# platform.net
KiCad netlist of a schematic drawn in EAGLE
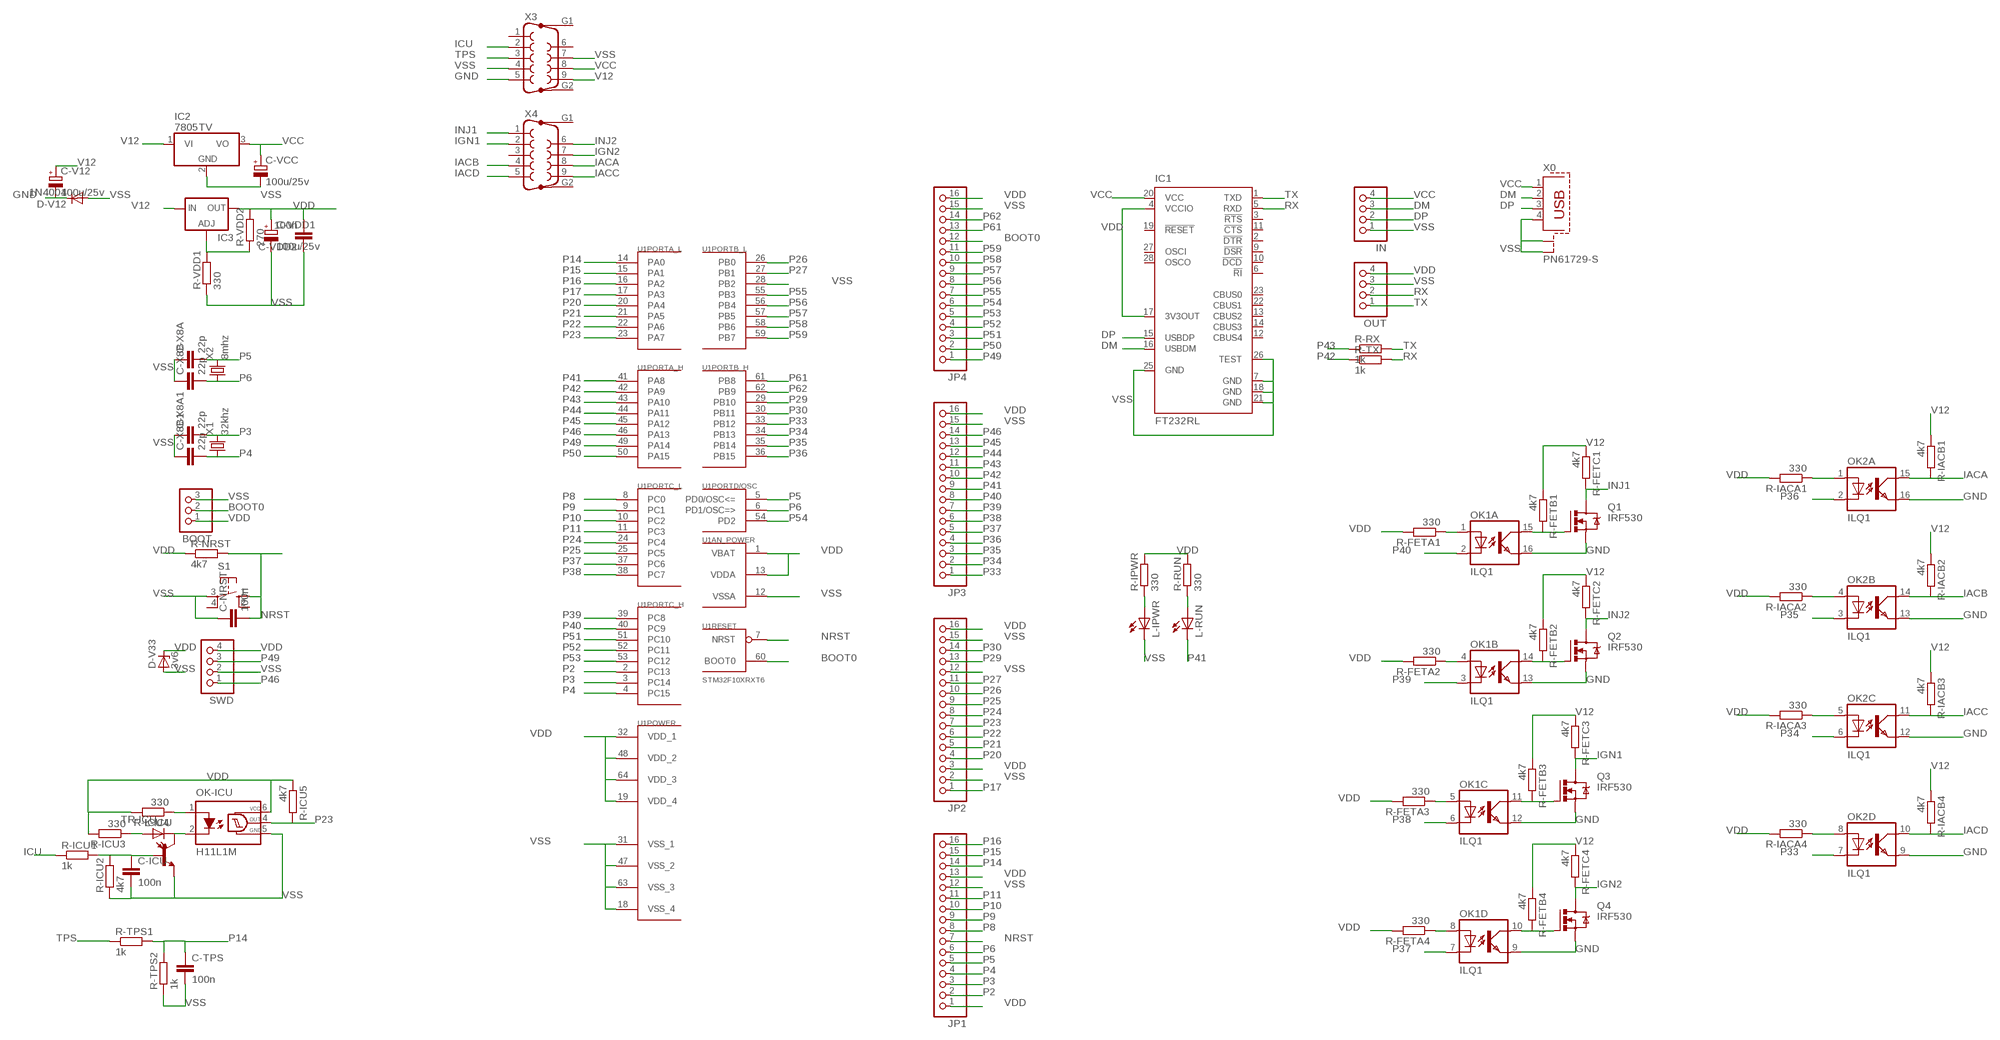
[diagram p0: schematic, sheet 1]

(export (version "E")
  (design (tool "Eeschema 10.0.6"))
  (components
    (comp (ref "BOOT")
      (value "PINHD-1X3")
      (footprint "eagle-import:1X03")
      (libsource (lib "eagle-import") (part "PINHD-1X3"))
    )
    (comp (ref "C-ICU")
      (value "100n")
      (footprint "eagle-import:C050-024X044")
      (libsource (lib "eagle-import") (part "C-EU050-024X044"))
    )
    (comp (ref "C-NRST")
      (value "100n")
      (footprint "eagle-import:C050-024X044")
      (libsource (lib "eagle-import") (part "C-EU050-024X044"))
    )
    (comp (ref "C-TPS")
      (value "100n")
      (footprint "eagle-import:C050-024X044")
      (libsource (lib "eagle-import") (part "C-EU050-024X044"))
    )
    (comp (ref "C-V12")
      (value "100u/25v")
      (footprint "eagle-import:E2-5")
      (libsource (lib "eagle-import") (part "CPOL-EUE2-5"))
    )
    (comp (ref "C-VCC")
      (value "100u/25v")
      (footprint "eagle-import:E2-5")
      (libsource (lib "eagle-import") (part "CPOL-EUE2-5"))
    )
    (comp (ref "C-VDD1")
      (value "100u/25v")
      (footprint "eagle-import:E2-5")
      (libsource (lib "eagle-import") (part "CPOL-EUE2-5"))
    )
    (comp (ref "C-VDD2")
      (value "100n")
      (footprint "eagle-import:C050-024X044")
      (libsource (lib "eagle-import") (part "C-EU050-024X044"))
    )
    (comp (ref "C-X8A")
      (value "22p")
      (footprint "eagle-import:C025-024X044")
      (libsource (lib "eagle-import") (part "C-EU025-024X044"))
    )
    (comp (ref "C-X8A1")
      (value "22p")
      (footprint "eagle-import:C025-024X044")
      (libsource (lib "eagle-import") (part "C-EU025-024X044"))
    )
    (comp (ref "C-X8B")
      (value "22p")
      (footprint "eagle-import:C025-024X044")
      (libsource (lib "eagle-import") (part "C-EU025-024X044"))
    )
    (comp (ref "C-X8B1")
      (value "22p")
      (footprint "eagle-import:C025-024X044")
      (libsource (lib "eagle-import") (part "C-EU025-024X044"))
    )
    (comp (ref "D-V12")
      (value "1N4004")
      (footprint "eagle-import:DO41-10")
      (libsource (lib "eagle-import") (part "1N4004"))
    )
    (comp (ref "D-V33")
      (value "3v6")
      (footprint "eagle-import:ZDIO-7.5")
      (libsource (lib "eagle-import") (part "ZENER-DIODEZD-7.5"))
    )
    (comp (ref "IC1")
      (value "FT232RL")
      (footprint "eagle-import:SSOP28")
      (libsource (lib "eagle-import") (part "FT232RL"))
    )
    (comp (ref "IC2")
      (value "7805TV")
      (footprint "eagle-import:TO220V")
      (libsource (lib "eagle-import") (part "78TV05"))
    )
    (comp (ref "IC3")
      (value "LM317TS")
      (footprint "eagle-import:317TS")
      (libsource (lib "eagle-import") (part "LM317TS"))
    )
    (comp (ref "IN")
      (value "PINHD-1X4")
      (footprint "eagle-import:1X04")
      (libsource (lib "eagle-import") (part "PINHD-1X4"))
    )
    (comp (ref "JP1")
      (value "PINHD-1X16")
      (footprint "eagle-import:1X16")
      (libsource (lib "eagle-import") (part "PINHD-1X16"))
    )
    (comp (ref "JP2")
      (value "PINHD-1X16")
      (footprint "eagle-import:1X16")
      (libsource (lib "eagle-import") (part "PINHD-1X16"))
    )
    (comp (ref "JP3")
      (value "PINHD-1X16")
      (footprint "eagle-import:1X16")
      (libsource (lib "eagle-import") (part "PINHD-1X16"))
    )
    (comp (ref "JP4")
      (value "PINHD-1X16")
      (footprint "eagle-import:1X16")
      (libsource (lib "eagle-import") (part "PINHD-1X16"))
    )
    (comp (ref "L-ICU")
      (value "LED3MM")
      (footprint "eagle-import:LED3MM")
      (libsource (lib "eagle-import") (part "LED3MM"))
    )
    (comp (ref "L-IPWR")
      (value "LED3MM")
      (footprint "eagle-import:LED3MM")
      (libsource (lib "eagle-import") (part "LED3MM"))
    )
    (comp (ref "L-RUN")
      (value "LED3MM")
      (footprint "eagle-import:LED3MM")
      (libsource (lib "eagle-import") (part "LED3MM"))
    )
    (comp (ref "OK-ICU")
      (value "H11L1M")
      (footprint "eagle-import:DIL06")
      (fields (field (name "MF") "FAIRCHILD SEMICONDUCTOR") (field (name "MPN") "H11L1-M"))
      (libsource (lib "eagle-import") (part "H11LM1"))
    )
    (comp (ref "OK1")
      (value "ILQ1")
      (footprint "eagle-import:DIL16")
      (fields (field (name "MF") "VISHAY/TELEFUNKEN"))
      (libsource (lib "eagle-import") (part "ILQ1"))
    )
    (comp (ref "OK2")
      (value "ILQ1")
      (footprint "eagle-import:DIL16")
      (fields (field (name "MF") "VISHAY/TELEFUNKEN"))
      (libsource (lib "eagle-import") (part "ILQ1"))
    )
    (comp (ref "OUT")
      (value "PINHD-1X4")
      (footprint "eagle-import:1X04")
      (libsource (lib "eagle-import") (part "PINHD-1X4"))
    )
    (comp (ref "Q1")
      (value "IRF530")
      (footprint "eagle-import:TO220BV")
      (libsource (lib "eagle-import") (part "IRF530"))
    )
    (comp (ref "Q2")
      (value "IRF530")
      (footprint "eagle-import:TO220BV")
      (libsource (lib "eagle-import") (part "IRF530"))
    )
    (comp (ref "Q3")
      (value "IRF530")
      (footprint "eagle-import:TO220BV")
      (libsource (lib "eagle-import") (part "IRF530"))
    )
    (comp (ref "Q4")
      (value "IRF530")
      (footprint "eagle-import:TO220BV")
      (libsource (lib "eagle-import") (part "IRF530"))
    )
    (comp (ref "R-FETA1")
      (value "330")
      (footprint "eagle-import:0204_7")
      (libsource (lib "eagle-import") (part "R-EU_0204/7"))
    )
    (comp (ref "R-FETA2")
      (value "330")
      (footprint "eagle-import:0204_7")
      (libsource (lib "eagle-import") (part "R-EU_0204/7"))
    )
    (comp (ref "R-FETA3")
      (value "330")
      (footprint "eagle-import:0204_7")
      (libsource (lib "eagle-import") (part "R-EU_0204/7"))
    )
    (comp (ref "R-FETA4")
      (value "330")
      (footprint "eagle-import:0204_7")
      (libsource (lib "eagle-import") (part "R-EU_0204/7"))
    )
    (comp (ref "R-FETB1")
      (value "4k7")
      (footprint "eagle-import:0204_7")
      (libsource (lib "eagle-import") (part "R-EU_0204/7"))
    )
    (comp (ref "R-FETB2")
      (value "4k7")
      (footprint "eagle-import:0204_7")
      (libsource (lib "eagle-import") (part "R-EU_0204/7"))
    )
    (comp (ref "R-FETB3")
      (value "4k7")
      (footprint "eagle-import:0204_7")
      (libsource (lib "eagle-import") (part "R-EU_0204/7"))
    )
    (comp (ref "R-FETB4")
      (value "4k7")
      (footprint "eagle-import:0204_7")
      (libsource (lib "eagle-import") (part "R-EU_0204/7"))
    )
    (comp (ref "R-FETC1")
      (value "4k7")
      (footprint "eagle-import:0204_7")
      (libsource (lib "eagle-import") (part "R-EU_0204/7"))
    )
    (comp (ref "R-FETC2")
      (value "4k7")
      (footprint "eagle-import:0204_7")
      (libsource (lib "eagle-import") (part "R-EU_0204/7"))
    )
    (comp (ref "R-FETC3")
      (value "4k7")
      (footprint "eagle-import:0204_7")
      (libsource (lib "eagle-import") (part "R-EU_0204/7"))
    )
    (comp (ref "R-FETC4")
      (value "4k7")
      (footprint "eagle-import:0204_7")
      (libsource (lib "eagle-import") (part "R-EU_0204/7"))
    )
    (comp (ref "R-IACA1")
      (value "330")
      (footprint "eagle-import:0204_7")
      (libsource (lib "eagle-import") (part "R-EU_0204/7"))
    )
    (comp (ref "R-IACA2")
      (value "330")
      (footprint "eagle-import:0204_7")
      (libsource (lib "eagle-import") (part "R-EU_0204/7"))
    )
    (comp (ref "R-IACA3")
      (value "330")
      (footprint "eagle-import:0204_7")
      (libsource (lib "eagle-import") (part "R-EU_0204/7"))
    )
    (comp (ref "R-IACA4")
      (value "330")
      (footprint "eagle-import:0204_7")
      (libsource (lib "eagle-import") (part "R-EU_0204/7"))
    )
    (comp (ref "R-IACB1")
      (value "4k7")
      (footprint "eagle-import:0204_7")
      (libsource (lib "eagle-import") (part "R-EU_0204/7"))
    )
    (comp (ref "R-IACB2")
      (value "4k7")
      (footprint "eagle-import:0204_7")
      (libsource (lib "eagle-import") (part "R-EU_0204/7"))
    )
    (comp (ref "R-IACB3")
      (value "4k7")
      (footprint "eagle-import:0204_7")
      (libsource (lib "eagle-import") (part "R-EU_0204/7"))
    )
    (comp (ref "R-IACB4")
      (value "4k7")
      (footprint "eagle-import:0204_7")
      (libsource (lib "eagle-import") (part "R-EU_0204/7"))
    )
    (comp (ref "R-ICU1")
      (value "1k")
      (footprint "eagle-import:0204_7")
      (libsource (lib "eagle-import") (part "R-EU_0204/7"))
    )
    (comp (ref "R-ICU2")
      (value "4k7")
      (footprint "eagle-import:0204_7")
      (libsource (lib "eagle-import") (part "R-EU_0204/7"))
    )
    (comp (ref "R-ICU3")
      (value "330")
      (footprint "eagle-import:0204_7")
      (libsource (lib "eagle-import") (part "R-EU_0204/7"))
    )
    (comp (ref "R-ICU4")
      (value "330")
      (footprint "eagle-import:0204_7")
      (libsource (lib "eagle-import") (part "R-EU_0204/7"))
    )
    (comp (ref "R-ICU5")
      (value "4k7")
      (footprint "eagle-import:0204_7")
      (libsource (lib "eagle-import") (part "R-EU_0204/7"))
    )
    (comp (ref "R-IPWR")
      (value "330")
      (footprint "eagle-import:0204_7")
      (libsource (lib "eagle-import") (part "R-EU_0204/7"))
    )
    (comp (ref "R-NRST")
      (value "4k7")
      (footprint "eagle-import:0204_7")
      (libsource (lib "eagle-import") (part "R-EU_0204/7"))
    )
    (comp (ref "R-RUN")
      (value "330")
      (footprint "eagle-import:0204_7")
      (libsource (lib "eagle-import") (part "R-EU_0204/7"))
    )
    (comp (ref "R-RX")
      (value "1k")
      (footprint "eagle-import:0204_7")
      (libsource (lib "eagle-import") (part "R-EU_0204/7"))
    )
    (comp (ref "R-TPS1")
      (value "1k")
      (footprint "eagle-import:0204_7")
      (libsource (lib "eagle-import") (part "R-EU_0204/7"))
    )
    (comp (ref "R-TPS2")
      (value "1k")
      (footprint "eagle-import:0204_7")
      (libsource (lib "eagle-import") (part "R-EU_0204/7"))
    )
    (comp (ref "R-TX")
      (value "1k")
      (footprint "eagle-import:0204_7")
      (libsource (lib "eagle-import") (part "R-EU_0204/7"))
    )
    (comp (ref "R-VDD1")
      (value "330")
      (footprint "eagle-import:0204_7")
      (libsource (lib "eagle-import") (part "R-EU_0204/7"))
    )
    (comp (ref "R-VDD2")
      (value "270")
      (footprint "eagle-import:0204_7")
      (libsource (lib "eagle-import") (part "R-EU_0204/7"))
    )
    (comp (ref "S1")
      (value "10-XX")
      (footprint "eagle-import:B3F-10XX")
      (fields (field (name "MPN") "B3F-1000"))
      (libsource (lib "eagle-import") (part "10-XX"))
    )
    (comp (ref "SWD")
      (value "PINHD-1X4")
      (footprint "eagle-import:1X04")
      (libsource (lib "eagle-import") (part "PINHD-1X4"))
    )
    (comp (ref "TR-ICU")
      (value "2N3904-NPN-TO92-EBC")
      (footprint "eagle-import:TO92-EBC")
      (libsource (lib "eagle-import") (part "-NPN-TO92-EBC2N3904"))
    )
    (comp (ref "U1")
      (value "STM32F10XRXT6")
      (footprint "eagle-import:TQFP64")
      (libsource (lib "eagle-import") (part "STM32F10XRXT6"))
    )
    (comp (ref "X0")
      (value "PN61729-S")
      (footprint "eagle-import:PN61729-S")
      (libsource (lib "eagle-import") (part "PN61729-S"))
    )
    (comp (ref "X1")
      (value "32khz")
      (footprint "eagle-import:TC26V")
      (libsource (lib "eagle-import") (part "CRYSTALTC26V"))
    )
    (comp (ref "X2")
      (value "8mhz")
      (footprint "eagle-import:HC49U-V")
      (libsource (lib "eagle-import") (part "CRYSTALHC49U-V"))
    )
    (comp (ref "X3")
      (value "F09HP")
      (footprint "eagle-import:F09HP")
      (libsource (lib "eagle-import") (part "F09HP"))
    )
    (comp (ref "X4")
      (value "F09HP")
      (footprint "eagle-import:F09HP")
      (libsource (lib "eagle-import") (part "F09HP"))
    )
  )
  (nets
    (net (code "1") (name "/BOOT0") (class "Default")
      (node (ref "BOOT") (pin "2") (pinfunction "2_2") (pintype "passive"))
      (node (ref "JP4") (pin "12") (pinfunction "12_12") (pintype "passive"))
      (node (ref "U1") (pin "60") (pinfunction "BOOT0_60") (pintype "input"))
    )
    (net (code "2") (name "/DM") (class "Default")
      (node (ref "IC1") (pin "16") (pinfunction "USBDM_16") (pintype "bidirectional"))
      (node (ref "IN") (pin "3") (pinfunction "3_3") (pintype "passive"))
      (node (ref "X0") (pin "2") (pinfunction "2_2") (pintype "passive"))
    )
    (net (code "3") (name "/DP") (class "Default")
      (node (ref "IC1") (pin "15") (pinfunction "USBDP_15") (pintype "bidirectional"))
      (node (ref "IN") (pin "2") (pinfunction "2_2") (pintype "passive"))
      (node (ref "X0") (pin "3") (pinfunction "3_3") (pintype "passive"))
    )
    (net (code "4") (name "/GND") (class "Default")
      (node (ref "C-V12") (pin "-") (pinfunction "-_-") (pintype "passive"))
      (node (ref "D-V12") (pin "C") (pinfunction "C_C") (pintype "passive"))
      (node (ref "OK1") (pin "12") (pinfunction "EMIT_12") (pintype "passive"))
      (node (ref "OK1") (pin "13") (pinfunction "EMIT_13") (pintype "passive"))
      (node (ref "OK1") (pin "16") (pinfunction "EMIT_16") (pintype "passive"))
      (node (ref "OK1") (pin "9") (pinfunction "EMIT_9") (pintype "passive"))
      (node (ref "OK2") (pin "12") (pinfunction "EMIT_12") (pintype "passive"))
      (node (ref "OK2") (pin "13") (pinfunction "EMIT_13") (pintype "passive"))
      (node (ref "OK2") (pin "16") (pinfunction "EMIT_16") (pintype "passive"))
      (node (ref "OK2") (pin "9") (pinfunction "EMIT_9") (pintype "passive"))
      (node (ref "Q1") (pin "S") (pinfunction "S_S") (pintype "passive"))
      (node (ref "Q2") (pin "S") (pinfunction "S_S") (pintype "passive"))
      (node (ref "Q3") (pin "S") (pinfunction "S_S") (pintype "passive"))
      (node (ref "Q4") (pin "S") (pinfunction "S_S") (pintype "passive"))
      (node (ref "X3") (pin "5") (pinfunction "5_5") (pintype "passive"))
    )
    (net (code "5") (name "/IACA") (class "Default")
      (node (ref "OK2") (pin "15") (pinfunction "COL_15") (pintype "passive"))
      (node (ref "R-IACB1") (pin "2") (pinfunction "2_2") (pintype "passive"))
      (node (ref "X4") (pin "8") (pinfunction "8_8") (pintype "passive"))
    )
    (net (code "6") (name "/IACB") (class "Default")
      (node (ref "OK2") (pin "14") (pinfunction "COL_14") (pintype "passive"))
      (node (ref "R-IACB2") (pin "2") (pinfunction "2_2") (pintype "passive"))
      (node (ref "X4") (pin "4") (pinfunction "4_4") (pintype "passive"))
    )
    (net (code "7") (name "/IACC") (class "Default")
      (node (ref "OK2") (pin "11") (pinfunction "COL_11") (pintype "passive"))
      (node (ref "R-IACB3") (pin "2") (pinfunction "2_2") (pintype "passive"))
      (node (ref "X4") (pin "9") (pinfunction "9_9") (pintype "passive"))
    )
    (net (code "8") (name "/IACD") (class "Default")
      (node (ref "OK2") (pin "10") (pinfunction "COL_10") (pintype "passive"))
      (node (ref "R-IACB4") (pin "2") (pinfunction "2_2") (pintype "passive"))
      (node (ref "X4") (pin "5") (pinfunction "5_5") (pintype "passive"))
    )
    (net (code "9") (name "/ICU") (class "Default")
      (node (ref "R-ICU1") (pin "1") (pinfunction "1_1") (pintype "passive"))
      (node (ref "X3") (pin "2") (pinfunction "2_2") (pintype "passive"))
    )
    (net (code "10") (name "/IGN1") (class "Default")
      (node (ref "Q3") (pin "D") (pinfunction "D_D") (pintype "passive"))
      (node (ref "R-FETC3") (pin "2") (pinfunction "2_2") (pintype "passive"))
      (node (ref "X4") (pin "2") (pinfunction "2_2") (pintype "passive"))
    )
    (net (code "11") (name "/IGN2") (class "Default")
      (node (ref "Q4") (pin "D") (pinfunction "D_D") (pintype "passive"))
      (node (ref "R-FETC4") (pin "2") (pinfunction "2_2") (pintype "passive"))
      (node (ref "X4") (pin "7") (pinfunction "7_7") (pintype "passive"))
    )
    (net (code "12") (name "/INJ1") (class "Default")
      (node (ref "Q1") (pin "D") (pinfunction "D_D") (pintype "passive"))
      (node (ref "R-FETC1") (pin "2") (pinfunction "2_2") (pintype "passive"))
      (node (ref "X4") (pin "1") (pinfunction "1_1") (pintype "passive"))
    )
    (net (code "13") (name "/INJ2") (class "Default")
      (node (ref "Q2") (pin "D") (pinfunction "D_D") (pintype "passive"))
      (node (ref "R-FETC2") (pin "2") (pinfunction "2_2") (pintype "passive"))
      (node (ref "X4") (pin "6") (pinfunction "6_6") (pintype "passive"))
    )
    (net (code "14") (name "/NRST") (class "Default")
      (node (ref "C-NRST") (pin "2") (pinfunction "2_2") (pintype "passive"))
      (node (ref "JP1") (pin "7") (pinfunction "7_7") (pintype "passive"))
      (node (ref "R-NRST") (pin "2") (pinfunction "2_2") (pintype "passive"))
      (node (ref "S1") (pin "1") (pinfunction "S_1") (pintype "passive"))
      (node (ref "U1") (pin "7") (pinfunction "NRST_7") (pintype "input"))
    )
    (net (code "15") (name "/P2") (class "Default")
      (node (ref "JP1") (pin "2") (pinfunction "2_2") (pintype "passive"))
      (node (ref "U1") (pin "2") (pinfunction "PC13_2") (pintype "bidirectional"))
    )
    (net (code "16") (name "/P3") (class "Default")
      (node (ref "C-X8A1") (pin "2") (pinfunction "2_2") (pintype "passive"))
      (node (ref "JP1") (pin "3") (pinfunction "3_3") (pintype "passive"))
      (node (ref "U1") (pin "3") (pinfunction "PC14_3") (pintype "bidirectional"))
      (node (ref "X1") (pin "2") (pinfunction "2_2") (pintype "passive"))
    )
    (net (code "17") (name "/P4") (class "Default")
      (node (ref "C-X8B1") (pin "2") (pinfunction "2_2") (pintype "passive"))
      (node (ref "JP1") (pin "4") (pinfunction "4_4") (pintype "passive"))
      (node (ref "U1") (pin "4") (pinfunction "PC15_4") (pintype "bidirectional"))
      (node (ref "X1") (pin "1") (pinfunction "1_1") (pintype "passive"))
    )
    (net (code "18") (name "/P5") (class "Default")
      (node (ref "C-X8A") (pin "2") (pinfunction "2_2") (pintype "passive"))
      (node (ref "JP1") (pin "5") (pinfunction "5_5") (pintype "passive"))
      (node (ref "U1") (pin "5") (pinfunction "PD0/OSC<=_5") (pintype "bidirectional"))
      (node (ref "X2") (pin "2") (pinfunction "2_2") (pintype "passive"))
    )
    (net (code "19") (name "/P6") (class "Default")
      (node (ref "C-X8B") (pin "2") (pinfunction "2_2") (pintype "passive"))
      (node (ref "JP1") (pin "6") (pinfunction "6_6") (pintype "passive"))
      (node (ref "U1") (pin "6") (pinfunction "PD1/OSC=>_6") (pintype "bidirectional"))
      (node (ref "X2") (pin "1") (pinfunction "1_1") (pintype "passive"))
    )
    (net (code "20") (name "/P8") (class "Default")
      (node (ref "JP1") (pin "8") (pinfunction "8_8") (pintype "passive"))
      (node (ref "U1") (pin "8") (pinfunction "PC0_8") (pintype "bidirectional"))
    )
    (net (code "21") (name "/P9") (class "Default")
      (node (ref "JP1") (pin "9") (pinfunction "9_9") (pintype "passive"))
      (node (ref "U1") (pin "9") (pinfunction "PC1_9") (pintype "bidirectional"))
    )
    (net (code "22") (name "/P10") (class "Default")
      (node (ref "JP1") (pin "10") (pinfunction "10_10") (pintype "passive"))
      (node (ref "U1") (pin "10") (pinfunction "PC2_10") (pintype "bidirectional"))
    )
    (net (code "23") (name "/P11") (class "Default")
      (node (ref "JP1") (pin "11") (pinfunction "11_11") (pintype "passive"))
      (node (ref "U1") (pin "11") (pinfunction "PC3_11") (pintype "bidirectional"))
    )
    (net (code "24") (name "/P14") (class "Default")
      (node (ref "C-TPS") (pin "1") (pinfunction "1_1") (pintype "passive"))
      (node (ref "JP1") (pin "14") (pinfunction "14_14") (pintype "passive"))
      (node (ref "R-TPS1") (pin "2") (pinfunction "2_2") (pintype "passive"))
      (node (ref "R-TPS2") (pin "2") (pinfunction "2_2") (pintype "passive"))
      (node (ref "U1") (pin "14") (pinfunction "PA0_14") (pintype "bidirectional"))
    )
    (net (code "25") (name "/P15") (class "Default")
      (node (ref "JP1") (pin "15") (pinfunction "15_15") (pintype "passive"))
      (node (ref "U1") (pin "15") (pinfunction "PA1_15") (pintype "bidirectional"))
    )
    (net (code "26") (name "/P16") (class "Default")
      (node (ref "JP1") (pin "16") (pinfunction "16_16") (pintype "passive"))
      (node (ref "U1") (pin "16") (pinfunction "PA2_16") (pintype "bidirectional"))
    )
    (net (code "27") (name "/P17") (class "Default")
      (node (ref "JP2") (pin "1") (pinfunction "1_1") (pintype "passive"))
      (node (ref "U1") (pin "17") (pinfunction "PA3_17") (pintype "bidirectional"))
    )
    (net (code "28") (name "/P20") (class "Default")
      (node (ref "JP2") (pin "4") (pinfunction "4_4") (pintype "passive"))
      (node (ref "U1") (pin "20") (pinfunction "PA4_20") (pintype "bidirectional"))
    )
    (net (code "29") (name "/P21") (class "Default")
      (node (ref "JP2") (pin "5") (pinfunction "5_5") (pintype "passive"))
      (node (ref "U1") (pin "21") (pinfunction "PA5_21") (pintype "bidirectional"))
    )
    (net (code "30") (name "/P22") (class "Default")
      (node (ref "JP2") (pin "6") (pinfunction "6_6") (pintype "passive"))
      (node (ref "U1") (pin "22") (pinfunction "PA6_22") (pintype "bidirectional"))
    )
    (net (code "31") (name "/P23") (class "Default")
      (node (ref "JP2") (pin "7") (pinfunction "7_7") (pintype "passive"))
      (node (ref "OK-ICU") (pin "4") (pinfunction "OUT_4") (pintype "output"))
      (node (ref "R-ICU5") (pin "2") (pinfunction "2_2") (pintype "passive"))
      (node (ref "U1") (pin "23") (pinfunction "PA7_23") (pintype "bidirectional"))
    )
    (net (code "32") (name "/P24") (class "Default")
      (node (ref "JP2") (pin "8") (pinfunction "8_8") (pintype "passive"))
      (node (ref "U1") (pin "24") (pinfunction "PC4_24") (pintype "bidirectional"))
    )
    (net (code "33") (name "/P25") (class "Default")
      (node (ref "JP2") (pin "9") (pinfunction "9_9") (pintype "passive"))
      (node (ref "U1") (pin "25") (pinfunction "PC5_25") (pintype "bidirectional"))
    )
    (net (code "34") (name "/P26") (class "Default")
      (node (ref "JP2") (pin "10") (pinfunction "10_10") (pintype "passive"))
      (node (ref "U1") (pin "26") (pinfunction "PB0_26") (pintype "bidirectional"))
    )
    (net (code "35") (name "/P27") (class "Default")
      (node (ref "JP2") (pin "11") (pinfunction "11_11") (pintype "passive"))
      (node (ref "U1") (pin "27") (pinfunction "PB1_27") (pintype "bidirectional"))
    )
    (net (code "36") (name "/P29") (class "Default")
      (node (ref "JP2") (pin "13") (pinfunction "13_13") (pintype "passive"))
      (node (ref "U1") (pin "29") (pinfunction "PB10_29") (pintype "bidirectional"))
    )
    (net (code "37") (name "/P30") (class "Default")
      (node (ref "JP2") (pin "14") (pinfunction "14_14") (pintype "passive"))
      (node (ref "U1") (pin "30") (pinfunction "PB11_30") (pintype "bidirectional"))
    )
    (net (code "38") (name "/P33") (class "Default")
      (node (ref "JP3") (pin "1") (pinfunction "1_1") (pintype "passive"))
      (node (ref "OK2") (pin "7") (pinfunction "C_7") (pintype "passive"))
      (node (ref "U1") (pin "33") (pinfunction "PB12_33") (pintype "bidirectional"))
    )
    (net (code "39") (name "/P34") (class "Default")
      (node (ref "JP3") (pin "2") (pinfunction "2_2") (pintype "passive"))
      (node (ref "OK2") (pin "6") (pinfunction "C_6") (pintype "passive"))
      (node (ref "U1") (pin "34") (pinfunction "PB13_34") (pintype "bidirectional"))
    )
    (net (code "40") (name "/P35") (class "Default")
      (node (ref "JP3") (pin "3") (pinfunction "3_3") (pintype "passive"))
      (node (ref "OK2") (pin "3") (pinfunction "C_3") (pintype "passive"))
      (node (ref "U1") (pin "35") (pinfunction "PB14_35") (pintype "bidirectional"))
    )
    (net (code "41") (name "/P36") (class "Default")
      (node (ref "JP3") (pin "4") (pinfunction "4_4") (pintype "passive"))
      (node (ref "OK2") (pin "2") (pinfunction "C_2") (pintype "passive"))
      (node (ref "U1") (pin "36") (pinfunction "PB15_36") (pintype "bidirectional"))
    )
    (net (code "42") (name "/P37") (class "Default")
      (node (ref "JP3") (pin "5") (pinfunction "5_5") (pintype "passive"))
      (node (ref "OK1") (pin "7") (pinfunction "C_7") (pintype "passive"))
      (node (ref "U1") (pin "37") (pinfunction "PC6_37") (pintype "bidirectional"))
    )
    (net (code "43") (name "/P38") (class "Default")
      (node (ref "JP3") (pin "6") (pinfunction "6_6") (pintype "passive"))
      (node (ref "OK1") (pin "6") (pinfunction "C_6") (pintype "passive"))
      (node (ref "U1") (pin "38") (pinfunction "PC7_38") (pintype "bidirectional"))
    )
    (net (code "44") (name "/P39") (class "Default")
      (node (ref "JP3") (pin "7") (pinfunction "7_7") (pintype "passive"))
      (node (ref "OK1") (pin "3") (pinfunction "C_3") (pintype "passive"))
      (node (ref "U1") (pin "39") (pinfunction "PC8_39") (pintype "bidirectional"))
    )
    (net (code "45") (name "/P40") (class "Default")
      (node (ref "JP3") (pin "8") (pinfunction "8_8") (pintype "passive"))
      (node (ref "OK1") (pin "2") (pinfunction "C_2") (pintype "passive"))
      (node (ref "U1") (pin "40") (pinfunction "PC9_40") (pintype "bidirectional"))
    )
    (net (code "46") (name "/P41") (class "Default")
      (node (ref "JP3") (pin "9") (pinfunction "9_9") (pintype "passive"))
      (node (ref "L-RUN") (pin "K") (pinfunction "C_K") (pintype "passive"))
      (node (ref "U1") (pin "41") (pinfunction "PA8_41") (pintype "bidirectional"))
    )
    (net (code "47") (name "/P42") (class "Default")
      (node (ref "JP3") (pin "10") (pinfunction "10_10") (pintype "passive"))
      (node (ref "R-TX") (pin "1") (pinfunction "1_1") (pintype "passive"))
      (node (ref "U1") (pin "42") (pinfunction "PA9_42") (pintype "bidirectional"))
    )
    (net (code "48") (name "/P43") (class "Default")
      (node (ref "JP3") (pin "11") (pinfunction "11_11") (pintype "passive"))
      (node (ref "R-RX") (pin "1") (pinfunction "1_1") (pintype "passive"))
      (node (ref "U1") (pin "43") (pinfunction "PA10_43") (pintype "bidirectional"))
    )
    (net (code "49") (name "/P44") (class "Default")
      (node (ref "JP3") (pin "12") (pinfunction "12_12") (pintype "passive"))
      (node (ref "U1") (pin "44") (pinfunction "PA11_44") (pintype "bidirectional"))
    )
    (net (code "50") (name "/P45") (class "Default")
      (node (ref "JP3") (pin "13") (pinfunction "13_13") (pintype "passive"))
      (node (ref "U1") (pin "45") (pinfunction "PA12_45") (pintype "bidirectional"))
    )
    (net (code "51") (name "/P46") (class "Default")
      (node (ref "JP3") (pin "14") (pinfunction "14_14") (pintype "passive"))
      (node (ref "SWD") (pin "1") (pinfunction "1_1") (pintype "passive"))
      (node (ref "U1") (pin "46") (pinfunction "PA13_46") (pintype "bidirectional"))
    )
    (net (code "52") (name "/P49") (class "Default")
      (node (ref "JP4") (pin "1") (pinfunction "1_1") (pintype "passive"))
      (node (ref "SWD") (pin "3") (pinfunction "3_3") (pintype "passive"))
      (node (ref "U1") (pin "49") (pinfunction "PA14_49") (pintype "bidirectional"))
    )
    (net (code "53") (name "/P50") (class "Default")
      (node (ref "JP4") (pin "2") (pinfunction "2_2") (pintype "passive"))
      (node (ref "U1") (pin "50") (pinfunction "PA15_50") (pintype "bidirectional"))
    )
    (net (code "54") (name "/P51") (class "Default")
      (node (ref "JP4") (pin "3") (pinfunction "3_3") (pintype "passive"))
      (node (ref "U1") (pin "51") (pinfunction "PC10_51") (pintype "bidirectional"))
    )
    (net (code "55") (name "/P52") (class "Default")
      (node (ref "JP4") (pin "4") (pinfunction "4_4") (pintype "passive"))
      (node (ref "U1") (pin "52") (pinfunction "PC11_52") (pintype "bidirectional"))
    )
    (net (code "56") (name "/P53") (class "Default")
      (node (ref "JP4") (pin "5") (pinfunction "5_5") (pintype "passive"))
      (node (ref "U1") (pin "53") (pinfunction "PC12_53") (pintype "bidirectional"))
    )
    (net (code "57") (name "/P54") (class "Default")
      (node (ref "JP4") (pin "6") (pinfunction "6_6") (pintype "passive"))
      (node (ref "U1") (pin "54") (pinfunction "PD2_54") (pintype "bidirectional"))
    )
    (net (code "58") (name "/P55") (class "Default")
      (node (ref "JP4") (pin "7") (pinfunction "7_7") (pintype "passive"))
      (node (ref "U1") (pin "55") (pinfunction "PB3_55") (pintype "bidirectional"))
    )
    (net (code "59") (name "/P56") (class "Default")
      (node (ref "JP4") (pin "8") (pinfunction "8_8") (pintype "passive"))
      (node (ref "U1") (pin "56") (pinfunction "PB4_56") (pintype "bidirectional"))
    )
    (net (code "60") (name "/P57") (class "Default")
      (node (ref "JP4") (pin "9") (pinfunction "9_9") (pintype "passive"))
      (node (ref "U1") (pin "57") (pinfunction "PB5_57") (pintype "bidirectional"))
    )
    (net (code "61") (name "/P58") (class "Default")
      (node (ref "JP4") (pin "10") (pinfunction "10_10") (pintype "passive"))
      (node (ref "U1") (pin "58") (pinfunction "PB6_58") (pintype "bidirectional"))
    )
    (net (code "62") (name "/P59") (class "Default")
      (node (ref "JP4") (pin "11") (pinfunction "11_11") (pintype "passive"))
      (node (ref "U1") (pin "59") (pinfunction "PB7_59") (pintype "bidirectional"))
    )
    (net (code "63") (name "/P61") (class "Default")
      (node (ref "JP4") (pin "13") (pinfunction "13_13") (pintype "passive"))
      (node (ref "U1") (pin "61") (pinfunction "PB8_61") (pintype "bidirectional"))
    )
    (net (code "64") (name "/P62") (class "Default")
      (node (ref "JP4") (pin "14") (pinfunction "14_14") (pintype "passive"))
      (node (ref "U1") (pin "62") (pinfunction "PB9_62") (pintype "bidirectional"))
    )
    (net (code "65") (name "/RX") (class "Default")
      (node (ref "IC1") (pin "5") (pinfunction "RXD_5") (pintype "input"))
      (node (ref "OUT") (pin "2") (pinfunction "2_2") (pintype "passive"))
      (node (ref "R-TX") (pin "2") (pinfunction "2_2") (pintype "passive"))
    )
    (net (code "66") (name "/TPS") (class "Default")
      (node (ref "R-TPS1") (pin "1") (pinfunction "1_1") (pintype "passive"))
      (node (ref "X3") (pin "3") (pinfunction "3_3") (pintype "passive"))
    )
    (net (code "67") (name "/TX") (class "Default")
      (node (ref "IC1") (pin "1") (pinfunction "TXD_1") (pintype "output"))
      (node (ref "OUT") (pin "1") (pinfunction "1_1") (pintype "passive"))
      (node (ref "R-RX") (pin "2") (pinfunction "2_2") (pintype "passive"))
    )
    (net (code "68") (name "/V12") (class "Default")
      (node (ref "C-V12") (pin "+") (pinfunction "+_+") (pintype "passive"))
      (node (ref "IC2") (pin "1") (pinfunction "VI_1") (pintype "input"))
      (node (ref "IC3") (pin "3") (pinfunction "IN_3") (pintype "input"))
      (node (ref "R-FETB1") (pin "1") (pinfunction "1_1") (pintype "passive"))
      (node (ref "R-FETB2") (pin "1") (pinfunction "1_1") (pintype "passive"))
      (node (ref "R-FETB3") (pin "1") (pinfunction "1_1") (pintype "passive"))
      (node (ref "R-FETB4") (pin "1") (pinfunction "1_1") (pintype "passive"))
      (node (ref "R-FETC1") (pin "1") (pinfunction "1_1") (pintype "passive"))
      (node (ref "R-FETC2") (pin "1") (pinfunction "1_1") (pintype "passive"))
      (node (ref "R-FETC3") (pin "1") (pinfunction "1_1") (pintype "passive"))
      (node (ref "R-FETC4") (pin "1") (pinfunction "1_1") (pintype "passive"))
      (node (ref "R-IACB1") (pin "1") (pinfunction "1_1") (pintype "passive"))
      (node (ref "R-IACB2") (pin "1") (pinfunction "1_1") (pintype "passive"))
      (node (ref "R-IACB3") (pin "1") (pinfunction "1_1") (pintype "passive"))
      (node (ref "R-IACB4") (pin "1") (pinfunction "1_1") (pintype "passive"))
      (node (ref "X3") (pin "9") (pinfunction "9_9") (pintype "passive"))
    )
    (net (code "69") (name "/VCC") (class "Default")
      (node (ref "C-VCC") (pin "+") (pinfunction "+_+") (pintype "passive"))
      (node (ref "IC1") (pin "20") (pinfunction "VCC_20") (pintype "power_in"))
      (node (ref "IC2") (pin "3") (pinfunction "VO_3") (pintype "passive"))
      (node (ref "IN") (pin "4") (pinfunction "4_4") (pintype "passive"))
      (node (ref "X0") (pin "1") (pinfunction "1_1") (pintype "passive"))
      (node (ref "X3") (pin "8") (pinfunction "8_8") (pintype "passive"))
    )
    (net (code "70") (name "/VDD") (class "Default")
      (node (ref "BOOT") (pin "1") (pinfunction "1_1") (pintype "passive"))
      (node (ref "C-VDD1") (pin "+") (pinfunction "+_+") (pintype "passive"))
      (node (ref "C-VDD2") (pin "2") (pinfunction "2_2") (pintype "passive"))
      (node (ref "D-V33") (pin "C") (pinfunction "C_C") (pintype "passive"))
      (node (ref "IC1") (pin "17") (pinfunction "3V3OUT_17") (pintype "output"))
      (node (ref "IC1") (pin "4") (pinfunction "VCCIO_4") (pintype "power_in"))
      (node (ref "IC3") (pin "2") (pinfunction "OUT_2") (pintype "passive"))
      (node (ref "JP1") (pin "1") (pinfunction "1_1") (pintype "passive"))
      (node (ref "JP1") (pin "13") (pinfunction "13_13") (pintype "passive"))
      (node (ref "JP2") (pin "16") (pinfunction "16_16") (pintype "passive"))
      (node (ref "JP2") (pin "3") (pinfunction "3_3") (pintype "passive"))
      (node (ref "JP3") (pin "16") (pinfunction "16_16") (pintype "passive"))
      (node (ref "JP4") (pin "16") (pinfunction "16_16") (pintype "passive"))
      (node (ref "OK-ICU") (pin "6") (pinfunction "VCC_6") (pintype "power_in"))
      (node (ref "OUT") (pin "4") (pinfunction "4_4") (pintype "passive"))
      (node (ref "R-FETA1") (pin "2") (pinfunction "2_2") (pintype "passive"))
      (node (ref "R-FETA2") (pin "2") (pinfunction "2_2") (pintype "passive"))
      (node (ref "R-FETA3") (pin "2") (pinfunction "2_2") (pintype "passive"))
      (node (ref "R-FETA4") (pin "2") (pinfunction "2_2") (pintype "passive"))
      (node (ref "R-IACA1") (pin "2") (pinfunction "2_2") (pintype "passive"))
      (node (ref "R-IACA2") (pin "2") (pinfunction "2_2") (pintype "passive"))
      (node (ref "R-IACA3") (pin "2") (pinfunction "2_2") (pintype "passive"))
      (node (ref "R-IACA4") (pin "2") (pinfunction "2_2") (pintype "passive"))
      (node (ref "R-ICU3") (pin "2") (pinfunction "2_2") (pintype "passive"))
      (node (ref "R-ICU4") (pin "2") (pinfunction "2_2") (pintype "passive"))
      (node (ref "R-ICU5") (pin "1") (pinfunction "1_1") (pintype "passive"))
      (node (ref "R-IPWR") (pin "2") (pinfunction "2_2") (pintype "passive"))
      (node (ref "R-NRST") (pin "1") (pinfunction "1_1") (pintype "passive"))
      (node (ref "R-RUN") (pin "2") (pinfunction "2_2") (pintype "passive"))
      (node (ref "R-VDD2") (pin "2") (pinfunction "2_2") (pintype "passive"))
      (node (ref "SWD") (pin "4") (pinfunction "4_4") (pintype "passive"))
      (node (ref "U1") (pin "1") (pinfunction "VBAT_1") (pintype "power_in"))
      (node (ref "U1") (pin "13") (pinfunction "VDDA_13") (pintype "power_in"))
      (node (ref "U1") (pin "19") (pinfunction "VDD_4_19") (pintype "power_in"))
      (node (ref "U1") (pin "32") (pinfunction "VDD_1_32") (pintype "power_in"))
      (node (ref "U1") (pin "48") (pinfunction "VDD_2_48") (pintype "power_in"))
      (node (ref "U1") (pin "64") (pinfunction "VDD_3_64") (pintype "power_in"))
    )
    (net (code "71") (name "/VSS") (class "Default")
      (node (ref "BOOT") (pin "3") (pinfunction "3_3") (pintype "passive"))
      (node (ref "C-ICU") (pin "2") (pinfunction "2_2") (pintype "passive"))
      (node (ref "C-NRST") (pin "1") (pinfunction "1_1") (pintype "passive"))
      (node (ref "C-TPS") (pin "2") (pinfunction "2_2") (pintype "passive"))
      (node (ref "C-VCC") (pin "-") (pinfunction "-_-") (pintype "passive"))
      (node (ref "C-VDD1") (pin "-") (pinfunction "-_-") (pintype "passive"))
      (node (ref "C-VDD2") (pin "1") (pinfunction "1_1") (pintype "passive"))
      (node (ref "C-X8A") (pin "1") (pinfunction "1_1") (pintype "passive"))
      (node (ref "C-X8A1") (pin "1") (pinfunction "1_1") (pintype "passive"))
      (node (ref "C-X8B") (pin "1") (pinfunction "1_1") (pintype "passive"))
      (node (ref "C-X8B1") (pin "1") (pinfunction "1_1") (pintype "passive"))
      (node (ref "D-V12") (pin "A") (pinfunction "A_A") (pintype "passive"))
      (node (ref "D-V33") (pin "A") (pinfunction "A_A") (pintype "passive"))
      (node (ref "IC1") (pin "18") (pinfunction "GND_18") (pintype "power_in"))
      (node (ref "IC1") (pin "21") (pinfunction "GND_21") (pintype "power_in"))
      (node (ref "IC1") (pin "25") (pinfunction "GND_25") (pintype "power_in"))
      (node (ref "IC1") (pin "26") (pinfunction "TEST_26") (pintype "input"))
      (node (ref "IC1") (pin "7") (pinfunction "GND_7") (pintype "power_in"))
      (node (ref "IC2") (pin "2") (pinfunction "GND_2") (pintype "passive"))
      (node (ref "IN") (pin "1") (pinfunction "1_1") (pintype "passive"))
      (node (ref "JP1") (pin "12") (pinfunction "12_12") (pintype "passive"))
      (node (ref "JP2") (pin "12") (pinfunction "12_12") (pintype "passive"))
      (node (ref "JP2") (pin "15") (pinfunction "15_15") (pintype "passive"))
      (node (ref "JP2") (pin "2") (pinfunction "2_2") (pintype "passive"))
      (node (ref "JP3") (pin "15") (pinfunction "15_15") (pintype "passive"))
      (node (ref "JP4") (pin "15") (pinfunction "15_15") (pintype "passive"))
      (node (ref "L-IPWR") (pin "K") (pinfunction "C_K") (pintype "passive"))
      (node (ref "OK-ICU") (pin "5") (pinfunction "GND_5") (pintype "power_in"))
      (node (ref "OUT") (pin "3") (pinfunction "3_3") (pintype "passive"))
      (node (ref "R-ICU2") (pin "1") (pinfunction "1_1") (pintype "passive"))
      (node (ref "R-TPS2") (pin "1") (pinfunction "1_1") (pintype "passive"))
      (node (ref "R-VDD1") (pin "1") (pinfunction "1_1") (pintype "passive"))
      (node (ref "S1") (pin "3") (pinfunction "P_3") (pintype "passive"))
      (node (ref "SWD") (pin "2") (pinfunction "2_2") (pintype "passive"))
      (node (ref "TR-ICU") (pin "E") (pinfunction "E_E") (pintype "passive"))
      (node (ref "U1") (pin "12") (pinfunction "VSSA_12") (pintype "power_in"))
      (node (ref "U1") (pin "18") (pinfunction "VSS_4_18") (pintype "power_in"))
      (node (ref "U1") (pin "28") (pinfunction "PB2_28") (pintype "bidirectional"))
      (node (ref "U1") (pin "31") (pinfunction "VSS_1_31") (pintype "power_in"))
      (node (ref "U1") (pin "47") (pinfunction "VSS_2_47") (pintype "power_in"))
      (node (ref "U1") (pin "63") (pinfunction "VSS_3_63") (pintype "power_in"))
      (node (ref "X0") (pin "4") (pinfunction "4_4") (pintype "passive"))
      (node (ref "X0") (pin "S1") (pinfunction "S1_S1") (pintype "passive"))
      (node (ref "X0") (pin "S2") (pinfunction "S2_S2") (pintype "passive"))
      (node (ref "X3") (pin "4") (pinfunction "4_4") (pintype "passive"))
      (node (ref "X3") (pin "7") (pinfunction "7_7") (pintype "passive"))
    )
    (net (code "72") (name "Net-(C-ICU-Pad1)") (class "Default")
      (node (ref "C-ICU") (pin "1") (pinfunction "1_1") (pintype "passive"))
      (node (ref "R-ICU1") (pin "2") (pinfunction "2_2") (pintype "passive"))
      (node (ref "R-ICU2") (pin "2") (pinfunction "2_2") (pintype "passive"))
      (node (ref "TR-ICU") (pin "B") (pinfunction "B_B") (pintype "passive"))
    )
    (net (code "73") (name "Net-(IC3-ADJ)") (class "Default")
      (node (ref "IC3") (pin "1") (pinfunction "ADJ_1") (pintype "input"))
      (node (ref "R-VDD1") (pin "2") (pinfunction "2_2") (pintype "passive"))
      (node (ref "R-VDD2") (pin "1") (pinfunction "1_1") (pintype "passive"))
    )
    (net (code "74") (name "Net-(L-ICU-C)") (class "Default")
      (node (ref "L-ICU") (pin "K") (pinfunction "C_K") (pintype "passive"))
      (node (ref "OK-ICU") (pin "2") (pinfunction "C_2") (pintype "passive"))
      (node (ref "TR-ICU") (pin "C") (pinfunction "C_C") (pintype "passive"))
    )
    (net (code "75") (name "Net-(L-ICU-PadA)") (class "Default")
      (node (ref "L-ICU") (pin "A") (pinfunction "A_A") (pintype "passive"))
      (node (ref "R-ICU3") (pin "1") (pinfunction "1_1") (pintype "passive"))
    )
    (net (code "76") (name "Net-(L-IPWR-PadA)") (class "Default")
      (node (ref "L-IPWR") (pin "A") (pinfunction "A_A") (pintype "passive"))
      (node (ref "R-IPWR") (pin "1") (pinfunction "1_1") (pintype "passive"))
    )
    (net (code "77") (name "Net-(L-RUN-PadA)") (class "Default")
      (node (ref "L-RUN") (pin "A") (pinfunction "A_A") (pintype "passive"))
      (node (ref "R-RUN") (pin "1") (pinfunction "1_1") (pintype "passive"))
    )
    (net (code "78") (name "Net-(OK-ICU-A)") (class "Default")
      (node (ref "OK-ICU") (pin "1") (pinfunction "A_1") (pintype "passive"))
      (node (ref "R-ICU4") (pin "1") (pinfunction "1_1") (pintype "passive"))
    )
    (net (code "79") (name "Net-(OK1A-A)") (class "Default")
      (node (ref "OK1") (pin "1") (pinfunction "A_1") (pintype "passive"))
      (node (ref "R-FETA1") (pin "1") (pinfunction "1_1") (pintype "passive"))
    )
    (net (code "80") (name "Net-(OK1A-COL)") (class "Default")
      (node (ref "OK1") (pin "15") (pinfunction "COL_15") (pintype "passive"))
      (node (ref "Q1") (pin "G") (pinfunction "G_G") (pintype "passive"))
      (node (ref "R-FETB1") (pin "2") (pinfunction "2_2") (pintype "passive"))
    )
    (net (code "81") (name "Net-(OK1B-A)") (class "Default")
      (node (ref "OK1") (pin "4") (pinfunction "A_4") (pintype "passive"))
      (node (ref "R-FETA2") (pin "1") (pinfunction "1_1") (pintype "passive"))
    )
    (net (code "82") (name "Net-(OK1B-COL)") (class "Default")
      (node (ref "OK1") (pin "14") (pinfunction "COL_14") (pintype "passive"))
      (node (ref "Q2") (pin "G") (pinfunction "G_G") (pintype "passive"))
      (node (ref "R-FETB2") (pin "2") (pinfunction "2_2") (pintype "passive"))
    )
    (net (code "83") (name "Net-(OK1C-A)") (class "Default")
      (node (ref "OK1") (pin "5") (pinfunction "A_5") (pintype "passive"))
      (node (ref "R-FETA3") (pin "1") (pinfunction "1_1") (pintype "passive"))
    )
    (net (code "84") (name "Net-(OK1C-COL)") (class "Default")
      (node (ref "OK1") (pin "11") (pinfunction "COL_11") (pintype "passive"))
      (node (ref "Q3") (pin "G") (pinfunction "G_G") (pintype "passive"))
      (node (ref "R-FETB3") (pin "2") (pinfunction "2_2") (pintype "passive"))
    )
    (net (code "85") (name "Net-(OK1D-A)") (class "Default")
      (node (ref "OK1") (pin "8") (pinfunction "A_8") (pintype "passive"))
      (node (ref "R-FETA4") (pin "1") (pinfunction "1_1") (pintype "passive"))
    )
    (net (code "86") (name "Net-(OK1D-COL)") (class "Default")
      (node (ref "OK1") (pin "10") (pinfunction "COL_10") (pintype "passive"))
      (node (ref "Q4") (pin "G") (pinfunction "G_G") (pintype "passive"))
      (node (ref "R-FETB4") (pin "2") (pinfunction "2_2") (pintype "passive"))
    )
    (net (code "87") (name "Net-(OK2A-A)") (class "Default")
      (node (ref "OK2") (pin "1") (pinfunction "A_1") (pintype "passive"))
      (node (ref "R-IACA1") (pin "1") (pinfunction "1_1") (pintype "passive"))
    )
    (net (code "88") (name "Net-(OK2B-A)") (class "Default")
      (node (ref "OK2") (pin "4") (pinfunction "A_4") (pintype "passive"))
      (node (ref "R-IACA2") (pin "1") (pinfunction "1_1") (pintype "passive"))
    )
    (net (code "89") (name "Net-(OK2C-A)") (class "Default")
      (node (ref "OK2") (pin "5") (pinfunction "A_5") (pintype "passive"))
      (node (ref "R-IACA3") (pin "1") (pinfunction "1_1") (pintype "passive"))
    )
    (net (code "90") (name "Net-(OK2D-A)") (class "Default")
      (node (ref "OK2") (pin "8") (pinfunction "A_8") (pintype "passive"))
      (node (ref "R-IACA4") (pin "1") (pinfunction "1_1") (pintype "passive"))
    )
    (net (code "91") (name "unconnected-(IC1-CBUS0-Pad23)") (class "Default")
      (node (ref "IC1") (pin "23") (pinfunction "CBUS0_23") (pintype "bidirectional"))
    )
    (net (code "92") (name "unconnected-(IC1-CBUS1-Pad22)") (class "Default")
      (node (ref "IC1") (pin "22") (pinfunction "CBUS1_22") (pintype "bidirectional"))
    )
    (net (code "93") (name "unconnected-(IC1-CBUS2-Pad13)") (class "Default")
      (node (ref "IC1") (pin "13") (pinfunction "CBUS2_13") (pintype "bidirectional"))
    )
    (net (code "94") (name "unconnected-(IC1-CBUS3-Pad14)") (class "Default")
      (node (ref "IC1") (pin "14") (pinfunction "CBUS3_14") (pintype "bidirectional"))
    )
    (net (code "95") (name "unconnected-(IC1-CBUS4-Pad12)") (class "Default")
      (node (ref "IC1") (pin "12") (pinfunction "CBUS4_12") (pintype "bidirectional"))
    )
    (net (code "96") (name "unconnected-(IC1-OSCI-Pad27)") (class "Default")
      (node (ref "IC1") (pin "27") (pinfunction "OSCI_27") (pintype "input"))
    )
    (net (code "97") (name "unconnected-(IC1-OSCO-Pad28)") (class "Default")
      (node (ref "IC1") (pin "28") (pinfunction "OSCO_28") (pintype "output"))
    )
    (net (code "98") (name "unconnected-(IC1-~{CTS}-Pad11)") (class "Default")
      (node (ref "IC1") (pin "11") (pinfunction "~{CTS}_11") (pintype "input"))
    )
    (net (code "99") (name "unconnected-(IC1-~{DCD}-Pad10)") (class "Default")
      (node (ref "IC1") (pin "10") (pinfunction "~{DCD}_10") (pintype "input"))
    )
    (net (code "100") (name "unconnected-(IC1-~{DSR}-Pad9)") (class "Default")
      (node (ref "IC1") (pin "9") (pinfunction "~{DSR}_9") (pintype "input"))
    )
    (net (code "101") (name "unconnected-(IC1-~{DTR}-Pad2)") (class "Default")
      (node (ref "IC1") (pin "2") (pinfunction "~{DTR}_2") (pintype "output"))
    )
    (net (code "102") (name "unconnected-(IC1-~{RESET}-Pad19)") (class "Default")
      (node (ref "IC1") (pin "19") (pinfunction "~{RESET}_19") (pintype "input"))
    )
    (net (code "103") (name "unconnected-(IC1-~{RI}-Pad6)") (class "Default")
      (node (ref "IC1") (pin "6") (pinfunction "~{RI}_6") (pintype "input"))
    )
    (net (code "104") (name "unconnected-(IC1-~{RTS}-Pad3)") (class "Default")
      (node (ref "IC1") (pin "3") (pinfunction "~{RTS}_3") (pintype "output"))
    )
    (net (code "105") (name "unconnected-(S1-P1-Pad4)") (class "Default")
      (node (ref "S1") (pin "4") (pinfunction "P1_4") (pintype "passive"))
    )
    (net (code "106") (name "unconnected-(S1-S1-Pad2)") (class "Default")
      (node (ref "S1") (pin "2") (pinfunction "S1_2") (pintype "passive"))
    )
    (net (code "107") (name "unconnected-(X3-Pad1)") (class "Default")
      (node (ref "X3") (pin "1") (pinfunction "1_1") (pintype "passive"))
    )
    (net (code "108") (name "unconnected-(X3-Pad6)") (class "Default")
      (node (ref "X3") (pin "6") (pinfunction "6_6") (pintype "passive"))
    )
    (net (code "109") (name "unconnected-(X3-PadG1)") (class "Default")
      (node (ref "X3") (pin "G1") (pinfunction "G1_G1") (pintype "passive"))
    )
    (net (code "110") (name "unconnected-(X3-PadG2)") (class "Default")
      (node (ref "X3") (pin "G2") (pinfunction "G2_G2") (pintype "passive"))
    )
    (net (code "111") (name "unconnected-(X4-Pad3)") (class "Default")
      (node (ref "X4") (pin "3") (pinfunction "3_3") (pintype "passive"))
    )
    (net (code "112") (name "unconnected-(X4-PadG1)") (class "Default")
      (node (ref "X4") (pin "G1") (pinfunction "G1_G1") (pintype "passive"))
    )
    (net (code "113") (name "unconnected-(X4-PadG2)") (class "Default")
      (node (ref "X4") (pin "G2") (pinfunction "G2_G2") (pintype "passive"))
    )
  )
)
